# Sheet.net
KiCad netlist of a schematic drawn in Altium Designer
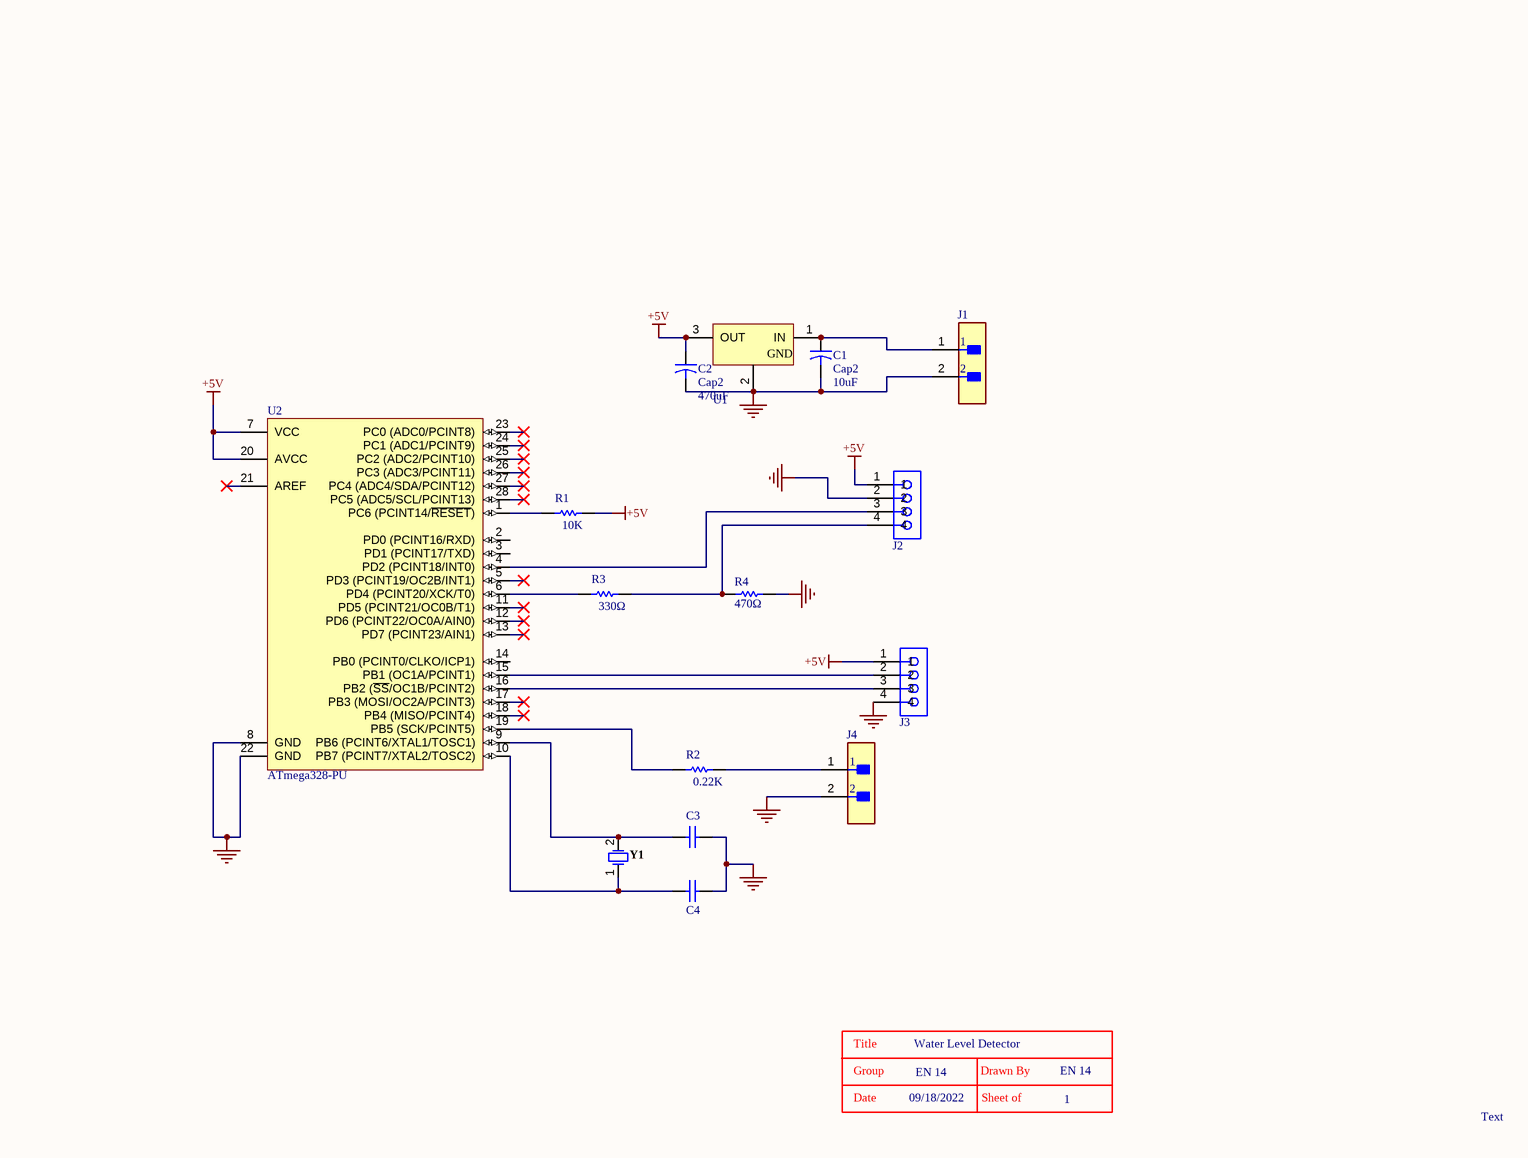
[diagram p0: Sheet.SchDoc]

(export (version "E")
  (design (tool "Eeschema 10.0.6"))
  (components
    (comp (ref "*") (value "Component_1") (libsource (lib "Title_Block") (part "Component_1")))
    (comp (ref "C1")
      (value "Cap2")
      (footprint "CAPR5-4X5")
      (description "Capacitor")
      (fields (field (name "ALTIUM_VALUE") "10uF") (field (name "PUBLISHER") "Altium Limited"))
      (libsource (lib "Miscellaneous Devices") (part "Cap2"))
    )
    (comp (ref "C2")
      (value "Cap2")
      (footprint "CAPR5-4X5")
      (description "Capacitor")
      (fields (field (name "ALTIUM_VALUE") "470uF") (field (name "PUBLISHER") "Altium Limited"))
      (libsource (lib "Miscellaneous Devices") (part "Cap2"))
    )
    (comp (ref "C3")
      (value "C315C220K1G5TA")
      (footprint "KEMT-C315-THT-2")
      (description "Capacitor, Ceramic, 22 pF, +/-10 %, 100 V, -55 to 125 degC, 2-Pin THD, RoHS, Bulk")
      (libsource (lib "Altium Content Vault") (part "CAP-NP-2"))
    )
    (comp (ref "C4")
      (value "C315C220K1G5TA")
      (footprint "KEMT-C315-THT-2")
      (description "Capacitor, Ceramic, 22 pF, +/-10 %, 100 V, -55 to 125 degC, 2-Pin THD, RoHS, Bulk")
      (libsource (lib "Altium Content Vault") (part "CAP-NP-2"))
    )
    (comp (ref "J1")
      (value "TSW-102-07-F-S")
      (footprint "FP-TSW-102-07-F-S-MFG")
      (description "CONN HEADER VERT 2POS 2.54MM")
      (libsource (lib "Altium Content Vault") (part "3bc925449376181038e59eaffc5286c"))
    )
    (comp (ref "J2")
      (value "MMS-104-01-T-SV")
      (footprint "SMTC-MMS-104-01-X-SV")
      (fields (field (name "MANUFACTURER") "Samtec"))
      (libsource (lib "Altium Content Vault") (part "SMTC-MMS-104-01-X-SV"))
    )
    (comp (ref "J3")
      (value "MMS-104-01-T-SV")
      (footprint "SMTC-MMS-104-01-X-SV")
      (fields (field (name "MANUFACTURER") "Samtec"))
      (libsource (lib "Altium Content Vault") (part "SMTC-MMS-104-01-X-SV"))
    )
    (comp (ref "J4")
      (value "TSW-102-07-L-S")
      (footprint "FP-TSW-102-07-L-S-MFG")
      (description "CONN HEADER VERT 2POS 2.54MM")
      (libsource (lib "Altium Content Vault") (part "3bc925449376181038e59eaffc5286c"))
    )
    (comp (ref "R1")
      (value "10K")
      (footprint "AXIAL-0.3")
      (description "Resistor")
      (fields (field (name "Comment") "Res1") (field (name "PUBLISHER") "Altium Limited"))
      (libsource (lib "Miscellaneous Devices") (part "Res1"))
    )
    (comp (ref "R2")
      (value "0.22K")
      (footprint "AXIAL-0.3")
      (description "Resistor")
      (fields (field (name "Comment") "Res1") (field (name "PUBLISHER") "Altium Limited"))
      (libsource (lib "Miscellaneous Devices") (part "Res1"))
    )
    (comp (ref "R3")
      (value "330Ω")
      (footprint "AXIAL-0.3")
      (description "Resistor")
      (fields (field (name "Comment") "Res1") (field (name "PUBLISHER") "Altium Limited"))
      (libsource (lib "Miscellaneous Devices") (part "Res1"))
    )
    (comp (ref "R4")
      (value "470Ω")
      (footprint "AXIAL-0.3")
      (description "Resistor")
      (fields (field (name "Comment") "Res1") (field (name "PUBLISHER") "Altium Limited"))
      (libsource (lib "Miscellaneous Devices") (part "Res1"))
    )
    (comp (ref "U1")
      (value "L7805CV")
      (footprint "TO220")
      (description "Positive Voltage Regulator, 5V, 3-Pin TO-220")
      (libsource (lib "Altium Content Vault") (part "PM-REG-L4940-SIL3"))
    )
    (comp (ref "U2")
      (value "ATmega328-PU")
      (footprint "28P3")
      (libsource (lib "Altium Content Vault") (part "MC-8B-ATM48-IL28"))
    )
    (comp (ref "Y1")
      (value "FOXSLF/160-20")
      (footprint "FOX-FOXSLF160-20")
      (description "Resistance Weld Thru-Hole Crystal, 16 MHz, -20 to 70 degC, 2-Pin THD, RoHS, Bulk")
      (fields (field (name "TOLERANCE") "1%"))
      (libsource (lib "Altium Content Vault") (part "XTAL-1-2-2"))
    )
  )
  (nets
    (net (code "1") (name "+5V") (class "Default")
      (node (ref "C2") (pin "1") (pinfunction "1_1") (pintype "passive"))
      (node (ref "J2") (pin "1") (pinfunction "1_1") (pintype "passive"))
      (node (ref "J3") (pin "1") (pinfunction "1_1") (pintype "passive"))
      (node (ref "R1") (pin "2") (pinfunction "2_2") (pintype "passive"))
      (node (ref "U1") (pin "3") (pinfunction "OUT_3") (pintype "power_in"))
      (node (ref "U2") (pin "20") (pinfunction "AVCC_20") (pintype "power_in"))
      (node (ref "U2") (pin "7") (pinfunction "VCC_7") (pintype "power_in"))
    )
    (net (code "2") (name "GND") (class "Default")
      (node (ref "C1") (pin "2") (pinfunction "2_2") (pintype "passive"))
      (node (ref "C2") (pin "2") (pinfunction "2_2") (pintype "passive"))
      (node (ref "C3") (pin "1") (pinfunction "1_1") (pintype "passive"))
      (node (ref "C4") (pin "2") (pinfunction "2_2") (pintype "passive"))
      (node (ref "J1") (pin "2") (pinfunction "2_2") (pintype "passive"))
      (node (ref "J2") (pin "2") (pinfunction "2_2") (pintype "passive"))
      (node (ref "J3") (pin "4") (pinfunction "4_4") (pintype "passive"))
      (node (ref "J4") (pin "2") (pinfunction "2_2") (pintype "passive"))
      (node (ref "R4") (pin "1") (pinfunction "1_1") (pintype "passive"))
      (node (ref "U1") (pin "2") (pinfunction "GND_2") (pintype "power_in"))
      (node (ref "U2") (pin "22") (pinfunction "GND_22") (pintype "power_in"))
      (node (ref "U2") (pin "8") (pinfunction "GND_8") (pintype "power_in"))
    )
    (net (code "3") (name "Net-(J2-Pad4)") (class "Default")
      (node (ref "J2") (pin "4") (pinfunction "4_4") (pintype "passive"))
      (node (ref "R3") (pin "2") (pinfunction "2_2") (pintype "passive"))
      (node (ref "R4") (pin "2") (pinfunction "2_2") (pintype "passive"))
    )
    (net (code "4") (name "Net-(J4-Pad1)") (class "Default")
      (node (ref "J4") (pin "1") (pinfunction "1_1") (pintype "passive"))
      (node (ref "R2") (pin "2") (pinfunction "2_2") (pintype "passive"))
    )
    (net (code "5") (name "Net-(U1-IN)") (class "Default")
      (node (ref "C1") (pin "1") (pinfunction "1_1") (pintype "passive"))
      (node (ref "J1") (pin "1") (pinfunction "1_1") (pintype "passive"))
      (node (ref "U1") (pin "1") (pinfunction "IN_1") (pintype "power_in"))
    )
    (net (code "6") (name "Net-(U2-PB1_(OC1A{slash}PCINT1))") (class "Default")
      (node (ref "J3") (pin "2") (pinfunction "2_2") (pintype "passive"))
      (node (ref "U2") (pin "15") (pinfunction "PB1_(OC1A/PCINT1)_15") (pintype "bidirectional"))
    )
    (net (code "7") (name "Net-(U2-PB2_(~{SS}{slash}OC1B{slash}PCINT2))") (class "Default")
      (node (ref "J3") (pin "3") (pinfunction "3_3") (pintype "passive"))
      (node (ref "U2") (pin "16") (pinfunction "PB2_(~{SS}/OC1B/PCINT2)_16") (pintype "bidirectional"))
    )
    (net (code "8") (name "Net-(U2-PB5_(SCK{slash}PCINT5))") (class "Default")
      (node (ref "R2") (pin "1") (pinfunction "1_1") (pintype "passive"))
      (node (ref "U2") (pin "19") (pinfunction "PB5_(SCK/PCINT5)_19") (pintype "bidirectional"))
    )
    (net (code "9") (name "Net-(U2-PB6_(PCINT6{slash}XTAL1{slash}TOSC1))") (class "Default")
      (node (ref "C3") (pin "2") (pinfunction "2_2") (pintype "passive"))
      (node (ref "U2") (pin "9") (pinfunction "PB6_(PCINT6/XTAL1/TOSC1)_9") (pintype "bidirectional"))
      (node (ref "Y1") (pin "2") (pinfunction "2_2") (pintype "passive"))
    )
    (net (code "10") (name "Net-(U2-PB7_(PCINT7{slash}XTAL2{slash}TOSC2))") (class "Default")
      (node (ref "C4") (pin "1") (pinfunction "1_1") (pintype "passive"))
      (node (ref "U2") (pin "10") (pinfunction "PB7_(PCINT7/XTAL2/TOSC2)_10") (pintype "bidirectional"))
      (node (ref "Y1") (pin "1") (pinfunction "1_1") (pintype "passive"))
    )
    (net (code "11") (name "Net-(U2-PC6_(PCINT14{slash}~{RESET}))") (class "Default")
      (node (ref "R1") (pin "1") (pinfunction "1_1") (pintype "passive"))
      (node (ref "U2") (pin "1") (pinfunction "PC6_(PCINT14/~{RESET})_1") (pintype "bidirectional"))
    )
    (net (code "12") (name "Net-(U2-PD2_(PCINT18{slash}INT0))") (class "Default")
      (node (ref "J2") (pin "3") (pinfunction "3_3") (pintype "passive"))
      (node (ref "U2") (pin "4") (pinfunction "PD2_(PCINT18/INT0)_4") (pintype "bidirectional"))
    )
    (net (code "13") (name "Net-(U2-PD4_(PCINT20{slash}XCK{slash}T0))") (class "Default")
      (node (ref "R3") (pin "1") (pinfunction "1_1") (pintype "passive"))
      (node (ref "U2") (pin "6") (pinfunction "PD4_(PCINT20/XCK/T0)_6") (pintype "bidirectional"))
    )
    (net (code "14") (name "unconnected-(U2-AREF-Pad21)") (class "Default")
      (node (ref "U2") (pin "21") (pinfunction "AREF_21") (pintype "power_in+no_connect"))
    )
    (net (code "15") (name "unconnected-(U2-PB0_(PCINT0{slash}CLKO{slash}ICP1)-Pad14)") (class "Default")
      (node (ref "U2") (pin "14") (pinfunction "PB0_(PCINT0/CLKO/ICP1)_14") (pintype "bidirectional"))
    )
    (net (code "16") (name "unconnected-(U2-PB3_(MOSI{slash}OC2A{slash}PCINT3)-Pad17)") (class "Default")
      (node (ref "U2") (pin "17") (pinfunction "PB3_(MOSI/OC2A/PCINT3)_17") (pintype "bidirectional+no_connect"))
    )
    (net (code "17") (name "unconnected-(U2-PB4_(MISO{slash}PCINT4)-Pad18)") (class "Default")
      (node (ref "U2") (pin "18") (pinfunction "PB4_(MISO/PCINT4)_18") (pintype "bidirectional+no_connect"))
    )
    (net (code "18") (name "unconnected-(U2-PC0_(ADC0{slash}PCINT8)-Pad23)") (class "Default")
      (node (ref "U2") (pin "23") (pinfunction "PC0_(ADC0/PCINT8)_23") (pintype "bidirectional+no_connect"))
    )
    (net (code "19") (name "unconnected-(U2-PC1_(ADC1{slash}PCINT9)-Pad24)") (class "Default")
      (node (ref "U2") (pin "24") (pinfunction "PC1_(ADC1/PCINT9)_24") (pintype "bidirectional+no_connect"))
    )
    (net (code "20") (name "unconnected-(U2-PC2_(ADC2{slash}PCINT10)-Pad25)") (class "Default")
      (node (ref "U2") (pin "25") (pinfunction "PC2_(ADC2/PCINT10)_25") (pintype "bidirectional+no_connect"))
    )
    (net (code "21") (name "unconnected-(U2-PC3_(ADC3{slash}PCINT11)-Pad26)") (class "Default")
      (node (ref "U2") (pin "26") (pinfunction "PC3_(ADC3/PCINT11)_26") (pintype "bidirectional+no_connect"))
    )
    (net (code "22") (name "unconnected-(U2-PC4_(ADC4{slash}SDA{slash}PCINT12)-Pad27)") (class "Default")
      (node (ref "U2") (pin "27") (pinfunction "PC4_(ADC4/SDA/PCINT12)_27") (pintype "bidirectional+no_connect"))
    )
    (net (code "23") (name "unconnected-(U2-PC5_(ADC5{slash}SCL{slash}PCINT13)-Pad28)") (class "Default")
      (node (ref "U2") (pin "28") (pinfunction "PC5_(ADC5/SCL/PCINT13)_28") (pintype "bidirectional+no_connect"))
    )
    (net (code "24") (name "unconnected-(U2-PD0_(PCINT16{slash}RXD)-Pad2)") (class "Default")
      (node (ref "U2") (pin "2") (pinfunction "PD0_(PCINT16/RXD)_2") (pintype "bidirectional"))
    )
    (net (code "25") (name "unconnected-(U2-PD1_(PCINT17{slash}TXD)-Pad3)") (class "Default")
      (node (ref "U2") (pin "3") (pinfunction "PD1_(PCINT17/TXD)_3") (pintype "bidirectional"))
    )
    (net (code "26") (name "unconnected-(U2-PD3_(PCINT19{slash}OC2B{slash}INT1)-Pad5)") (class "Default")
      (node (ref "U2") (pin "5") (pinfunction "PD3_(PCINT19/OC2B/INT1)_5") (pintype "bidirectional+no_connect"))
    )
    (net (code "27") (name "unconnected-(U2-PD5_(PCINT21{slash}OC0B{slash}T1)-Pad11)") (class "Default")
      (node (ref "U2") (pin "11") (pinfunction "PD5_(PCINT21/OC0B/T1)_11") (pintype "bidirectional+no_connect"))
    )
    (net (code "28") (name "unconnected-(U2-PD6_(PCINT22{slash}OC0A{slash}AIN0)-Pad12)") (class "Default")
      (node (ref "U2") (pin "12") (pinfunction "PD6_(PCINT22/OC0A/AIN0)_12") (pintype "bidirectional+no_connect"))
    )
    (net (code "29") (name "unconnected-(U2-PD7_(PCINT23{slash}AIN1)-Pad13)") (class "Default")
      (node (ref "U2") (pin "13") (pinfunction "PD7_(PCINT23/AIN1)_13") (pintype "bidirectional+no_connect"))
    )
  )
)
